# Schematic_SHERPA.net
KiCad netlist of a schematic drawn in Altium Designer
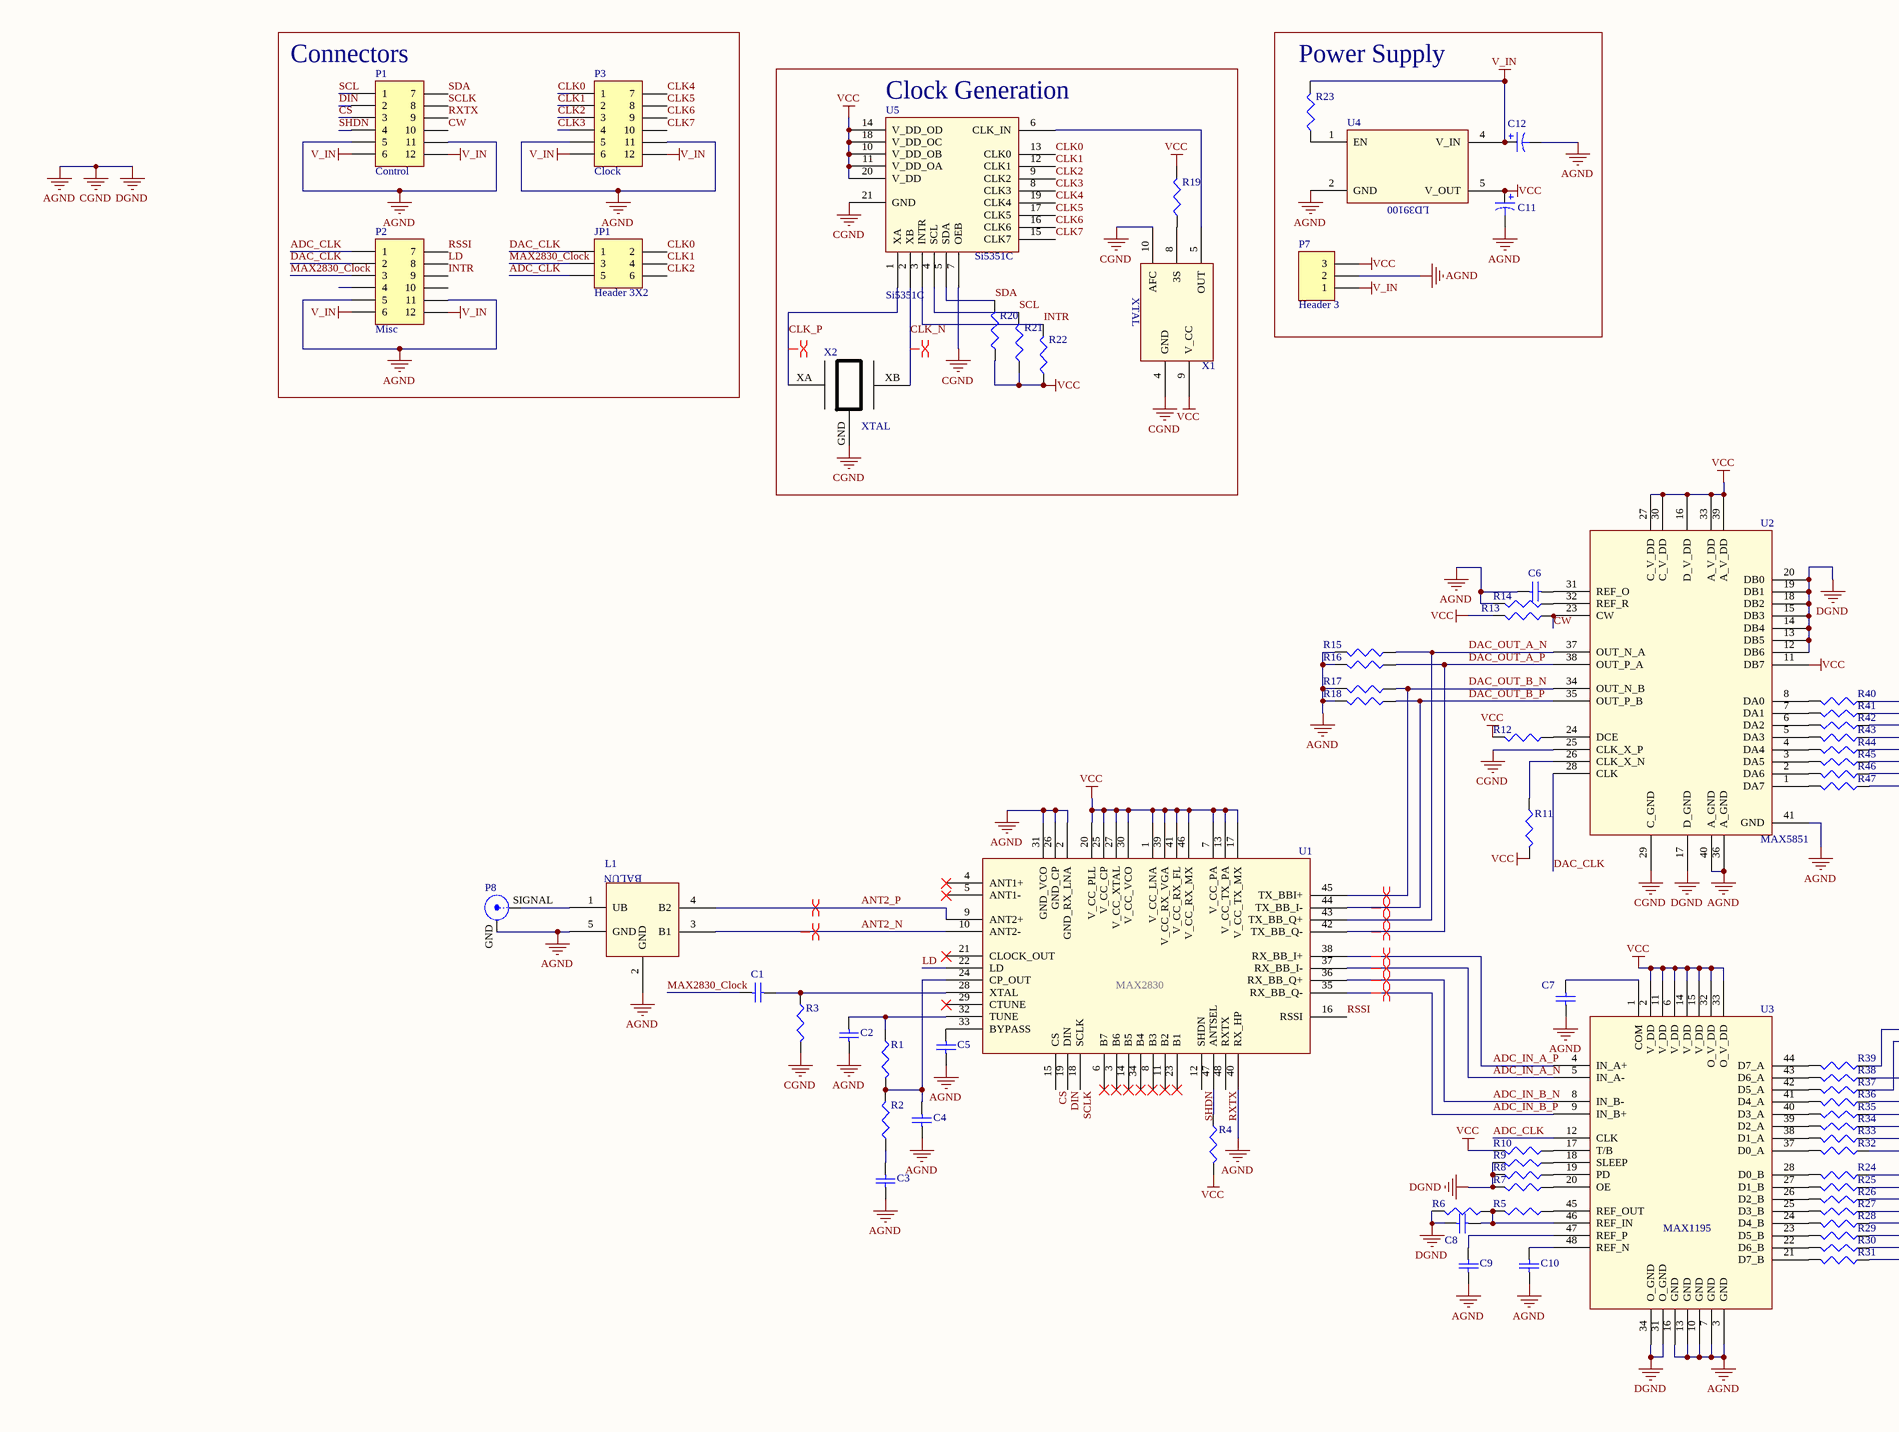
[diagram p0: Schematic_SHERPA.SchDoc, left]
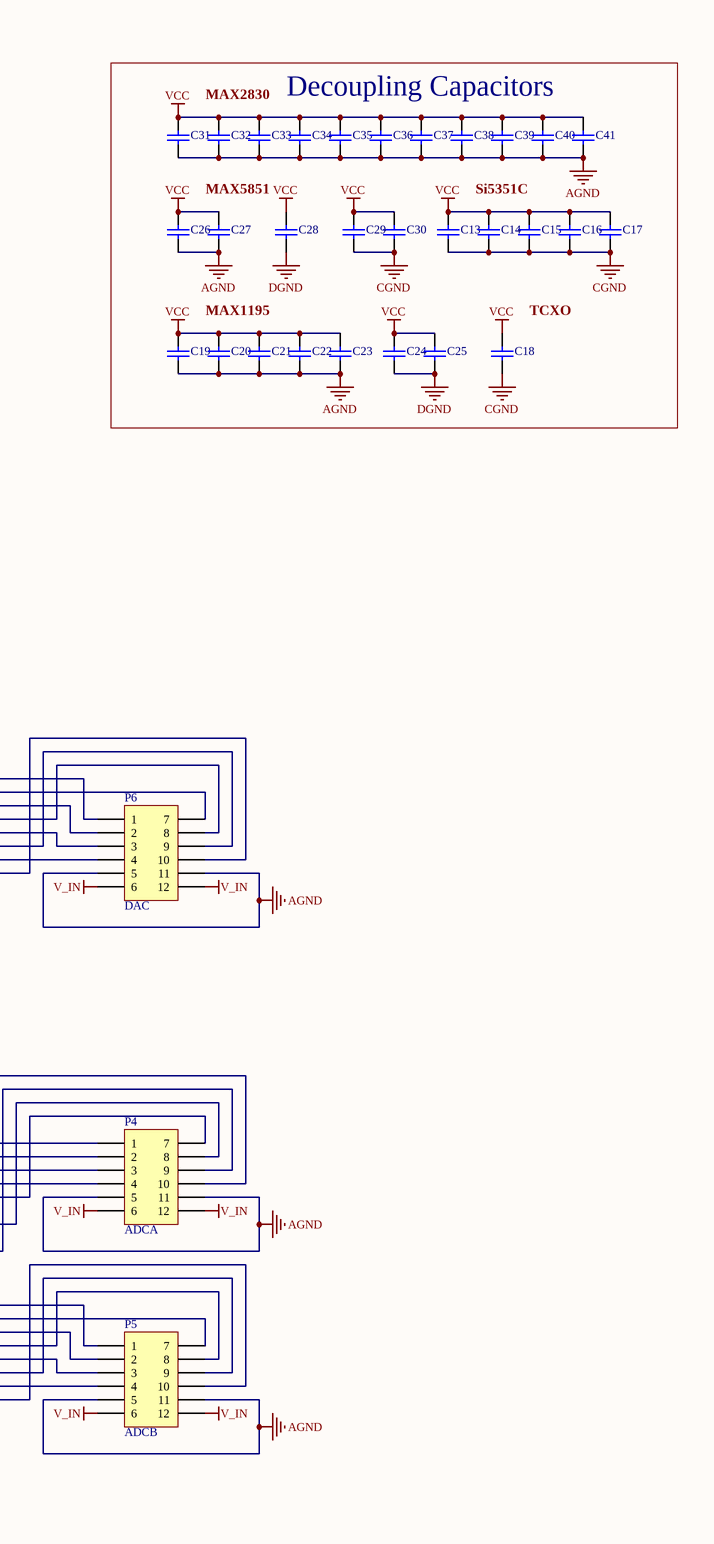
[diagram p1: Schematic_SHERPA.SchDoc, right]

(export (version "E")
  (design (tool "Eeschema 10.0.6"))
  (components
    (comp (ref "C1")
      (value "Cap Semi")
      (footprint "0402")
      (description "Capacitor (Semiconductor SIM Model)")
      (fields (field (name "PUBLISHER") "Altium Limited"))
      (libsource (lib "Miscellaneous Devices") (part "Cap Semi"))
    )
    (comp (ref "C2")
      (value "Cap Semi")
      (footprint "0402")
      (description "Capacitor (Semiconductor SIM Model)")
      (fields (field (name "PUBLISHER") "Altium Limited"))
      (libsource (lib "Miscellaneous Devices") (part "Cap Semi"))
    )
    (comp (ref "C3")
      (value "Cap Semi")
      (footprint "0402")
      (description "Capacitor (Semiconductor SIM Model)")
      (fields (field (name "PUBLISHER") "Altium Limited"))
      (libsource (lib "Miscellaneous Devices") (part "Cap Semi"))
    )
    (comp (ref "C4")
      (value "Cap Semi")
      (footprint "0402")
      (description "Capacitor (Semiconductor SIM Model)")
      (fields (field (name "PUBLISHER") "Altium Limited"))
      (libsource (lib "Miscellaneous Devices") (part "Cap Semi"))
    )
    (comp (ref "C5")
      (value "Cap Semi")
      (footprint "0402")
      (description "Capacitor (Semiconductor SIM Model)")
      (fields (field (name "PUBLISHER") "Altium Limited"))
      (libsource (lib "Miscellaneous Devices") (part "Cap Semi"))
    )
    (comp (ref "C6")
      (value "Cap Semi")
      (footprint "0402")
      (description "Capacitor (Semiconductor SIM Model)")
      (fields (field (name "PUBLISHER") "Altium Limited"))
      (libsource (lib "Miscellaneous Devices") (part "Cap Semi"))
    )
    (comp (ref "C7")
      (value "Cap Semi")
      (footprint "0402")
      (description "Capacitor (Semiconductor SIM Model)")
      (fields (field (name "PUBLISHER") "Altium Limited"))
      (libsource (lib "Miscellaneous Devices") (part "Cap Semi"))
    )
    (comp (ref "C8")
      (value "Cap Semi")
      (footprint "0402")
      (description "Capacitor (Semiconductor SIM Model)")
      (fields (field (name "PUBLISHER") "Altium Limited"))
      (libsource (lib "Miscellaneous Devices") (part "Cap Semi"))
    )
    (comp (ref "C9")
      (value "Cap Semi")
      (footprint "0402")
      (description "Capacitor (Semiconductor SIM Model)")
      (fields (field (name "PUBLISHER") "Altium Limited"))
      (libsource (lib "Miscellaneous Devices") (part "Cap Semi"))
    )
    (comp (ref "C10")
      (value "Cap Semi")
      (footprint "0402")
      (description "Capacitor (Semiconductor SIM Model)")
      (fields (field (name "PUBLISHER") "Altium Limited"))
      (libsource (lib "Miscellaneous Devices") (part "Cap Semi"))
    )
    (comp (ref "C11")
      (value "Cap Pol3")
      (footprint "C0805")
      (description "Polarized Capacitor (Surface Mount)")
      (fields (field (name "PUBLISHER") "Altium Limited"))
      (libsource (lib "Miscellaneous Devices") (part "Cap Pol3"))
    )
    (comp (ref "C12")
      (value "Cap Pol3")
      (footprint "C0805")
      (description "Polarized Capacitor (Surface Mount)")
      (fields (field (name "PUBLISHER") "Altium Limited"))
      (libsource (lib "Miscellaneous Devices") (part "Cap Pol3"))
    )
    (comp (ref "C13")
      (value "Cap Semi")
      (footprint "0402")
      (description "Capacitor (Semiconductor SIM Model)")
      (fields (field (name "PUBLISHER") "Altium Limited"))
      (libsource (lib "Miscellaneous Devices") (part "Cap Semi"))
    )
    (comp (ref "C14")
      (value "Cap Semi")
      (footprint "0402")
      (description "Capacitor (Semiconductor SIM Model)")
      (fields (field (name "PUBLISHER") "Altium Limited"))
      (libsource (lib "Miscellaneous Devices") (part "Cap Semi"))
    )
    (comp (ref "C15")
      (value "Cap Semi")
      (footprint "0402")
      (description "Capacitor (Semiconductor SIM Model)")
      (fields (field (name "PUBLISHER") "Altium Limited"))
      (libsource (lib "Miscellaneous Devices") (part "Cap Semi"))
    )
    (comp (ref "C16")
      (value "Cap Semi")
      (footprint "0402")
      (description "Capacitor (Semiconductor SIM Model)")
      (fields (field (name "PUBLISHER") "Altium Limited"))
      (libsource (lib "Miscellaneous Devices") (part "Cap Semi"))
    )
    (comp (ref "C17")
      (value "Cap Semi")
      (footprint "0402")
      (description "Capacitor (Semiconductor SIM Model)")
      (fields (field (name "PUBLISHER") "Altium Limited"))
      (libsource (lib "Miscellaneous Devices") (part "Cap Semi"))
    )
    (comp (ref "C18")
      (value "Cap Semi")
      (footprint "0402")
      (description "Capacitor (Semiconductor SIM Model)")
      (fields (field (name "PUBLISHER") "Altium Limited"))
      (libsource (lib "Miscellaneous Devices") (part "Cap Semi"))
    )
    (comp (ref "C19")
      (value "Cap Semi")
      (footprint "0402")
      (description "Capacitor (Semiconductor SIM Model)")
      (fields (field (name "PUBLISHER") "Altium Limited"))
      (libsource (lib "Miscellaneous Devices") (part "Cap Semi"))
    )
    (comp (ref "C20")
      (value "Cap Semi")
      (footprint "0402")
      (description "Capacitor (Semiconductor SIM Model)")
      (fields (field (name "PUBLISHER") "Altium Limited"))
      (libsource (lib "Miscellaneous Devices") (part "Cap Semi"))
    )
    (comp (ref "C21")
      (value "Cap Semi")
      (footprint "0402")
      (description "Capacitor (Semiconductor SIM Model)")
      (fields (field (name "PUBLISHER") "Altium Limited"))
      (libsource (lib "Miscellaneous Devices") (part "Cap Semi"))
    )
    (comp (ref "C22")
      (value "Cap Semi")
      (footprint "0402")
      (description "Capacitor (Semiconductor SIM Model)")
      (fields (field (name "PUBLISHER") "Altium Limited"))
      (libsource (lib "Miscellaneous Devices") (part "Cap Semi"))
    )
    (comp (ref "C23")
      (value "Cap Semi")
      (footprint "0402")
      (description "Capacitor (Semiconductor SIM Model)")
      (fields (field (name "PUBLISHER") "Altium Limited"))
      (libsource (lib "Miscellaneous Devices") (part "Cap Semi"))
    )
    (comp (ref "C24")
      (value "Cap Semi")
      (footprint "0402")
      (description "Capacitor (Semiconductor SIM Model)")
      (fields (field (name "PUBLISHER") "Altium Limited"))
      (libsource (lib "Miscellaneous Devices") (part "Cap Semi"))
    )
    (comp (ref "C25")
      (value "Cap Semi")
      (footprint "0402")
      (description "Capacitor (Semiconductor SIM Model)")
      (fields (field (name "PUBLISHER") "Altium Limited"))
      (libsource (lib "Miscellaneous Devices") (part "Cap Semi"))
    )
    (comp (ref "C26")
      (value "Cap Semi")
      (footprint "0402")
      (description "Capacitor (Semiconductor SIM Model)")
      (fields (field (name "PUBLISHER") "Altium Limited"))
      (libsource (lib "Miscellaneous Devices") (part "Cap Semi"))
    )
    (comp (ref "C27")
      (value "Cap Semi")
      (footprint "0402")
      (description "Capacitor (Semiconductor SIM Model)")
      (fields (field (name "PUBLISHER") "Altium Limited"))
      (libsource (lib "Miscellaneous Devices") (part "Cap Semi"))
    )
    (comp (ref "C28")
      (value "Cap Semi")
      (footprint "0402")
      (description "Capacitor (Semiconductor SIM Model)")
      (fields (field (name "PUBLISHER") "Altium Limited"))
      (libsource (lib "Miscellaneous Devices") (part "Cap Semi"))
    )
    (comp (ref "C29")
      (value "Cap Semi")
      (footprint "0402")
      (description "Capacitor (Semiconductor SIM Model)")
      (fields (field (name "PUBLISHER") "Altium Limited"))
      (libsource (lib "Miscellaneous Devices") (part "Cap Semi"))
    )
    (comp (ref "C30")
      (value "Cap Semi")
      (footprint "0402")
      (description "Capacitor (Semiconductor SIM Model)")
      (fields (field (name "PUBLISHER") "Altium Limited"))
      (libsource (lib "Miscellaneous Devices") (part "Cap Semi"))
    )
    (comp (ref "C31")
      (value "Cap Semi")
      (footprint "0402")
      (description "Capacitor (Semiconductor SIM Model)")
      (fields (field (name "PUBLISHER") "Altium Limited"))
      (libsource (lib "Miscellaneous Devices") (part "Cap Semi"))
    )
    (comp (ref "C32")
      (value "Cap Semi")
      (footprint "0402")
      (description "Capacitor (Semiconductor SIM Model)")
      (fields (field (name "PUBLISHER") "Altium Limited"))
      (libsource (lib "Miscellaneous Devices") (part "Cap Semi"))
    )
    (comp (ref "C33")
      (value "Cap Semi")
      (footprint "0402")
      (description "Capacitor (Semiconductor SIM Model)")
      (fields (field (name "PUBLISHER") "Altium Limited"))
      (libsource (lib "Miscellaneous Devices") (part "Cap Semi"))
    )
    (comp (ref "C34")
      (value "Cap Semi")
      (footprint "0402")
      (description "Capacitor (Semiconductor SIM Model)")
      (fields (field (name "PUBLISHER") "Altium Limited"))
      (libsource (lib "Miscellaneous Devices") (part "Cap Semi"))
    )
    (comp (ref "C35")
      (value "Cap Semi")
      (footprint "0402")
      (description "Capacitor (Semiconductor SIM Model)")
      (fields (field (name "PUBLISHER") "Altium Limited"))
      (libsource (lib "Miscellaneous Devices") (part "Cap Semi"))
    )
    (comp (ref "C36")
      (value "Cap Semi")
      (footprint "0402")
      (description "Capacitor (Semiconductor SIM Model)")
      (fields (field (name "PUBLISHER") "Altium Limited"))
      (libsource (lib "Miscellaneous Devices") (part "Cap Semi"))
    )
    (comp (ref "C37")
      (value "Cap Semi")
      (footprint "0402")
      (description "Capacitor (Semiconductor SIM Model)")
      (fields (field (name "PUBLISHER") "Altium Limited"))
      (libsource (lib "Miscellaneous Devices") (part "Cap Semi"))
    )
    (comp (ref "C38")
      (value "Cap Semi")
      (footprint "0402")
      (description "Capacitor (Semiconductor SIM Model)")
      (fields (field (name "PUBLISHER") "Altium Limited"))
      (libsource (lib "Miscellaneous Devices") (part "Cap Semi"))
    )
    (comp (ref "C39")
      (value "Cap Semi")
      (footprint "0402")
      (description "Capacitor (Semiconductor SIM Model)")
      (fields (field (name "PUBLISHER") "Altium Limited"))
      (libsource (lib "Miscellaneous Devices") (part "Cap Semi"))
    )
    (comp (ref "C40")
      (value "Cap Semi")
      (footprint "0402")
      (description "Capacitor (Semiconductor SIM Model)")
      (fields (field (name "PUBLISHER") "Altium Limited"))
      (libsource (lib "Miscellaneous Devices") (part "Cap Semi"))
    )
    (comp (ref "C41")
      (value "Cap Semi")
      (footprint "0402")
      (description "Capacitor (Semiconductor SIM Model)")
      (fields (field (name "PUBLISHER") "Altium Limited"))
      (libsource (lib "Miscellaneous Devices") (part "Cap Semi"))
    )
    (comp (ref "JP1")
      (value "Header 3X2")
      (footprint "HDR2X3")
      (description "Header, 3-Pin, Dual row")
      (fields (field (name "PUBLISHER") "Altium Limited"))
      (libsource (lib "Miscellaneous Connectors") (part "Header 3X2"))
    )
    (comp (ref "L1")
      (value "BALUN_2")
      (footprint "BALUN2")
      (libsource (lib "Schlib_SHERPA") (part "BALUN_2"))
    )
    (comp (ref "P1")
      (value "Control")
      (footprint "HDR2X6_CEN")
      (description "Header, 6-Pin, Dual row")
      (fields (field (name "PUBLISHER") "Altium Limited"))
      (libsource (lib "Miscellaneous Connectors") (part "Header 6X2A"))
    )
    (comp (ref "P2")
      (value "Misc")
      (footprint "HDR2X6_CEN")
      (description "Header, 6-Pin, Dual row")
      (fields (field (name "PUBLISHER") "Altium Limited"))
      (libsource (lib "Miscellaneous Connectors") (part "Header 6X2A"))
    )
    (comp (ref "P3")
      (value "Clock")
      (footprint "HDR2X6_CEN")
      (description "Header, 6-Pin, Dual row")
      (fields (field (name "PUBLISHER") "Altium Limited"))
      (libsource (lib "Miscellaneous Connectors") (part "Header 6X2A"))
    )
    (comp (ref "P4")
      (value "ADCA")
      (footprint "HDR2X6_CEN")
      (description "Header, 6-Pin, Dual row")
      (fields (field (name "PUBLISHER") "Altium Limited"))
      (libsource (lib "Miscellaneous Connectors") (part "Header 6X2A"))
    )
    (comp (ref "P5")
      (value "ADCB")
      (footprint "HDR2X6_CEN")
      (description "Header, 6-Pin, Dual row")
      (fields (field (name "PUBLISHER") "Altium Limited"))
      (libsource (lib "Miscellaneous Connectors") (part "Header 6X2A"))
    )
    (comp (ref "P6")
      (value "DAC")
      (footprint "HDR2X6_CEN")
      (description "Header, 6-Pin, Dual row")
      (fields (field (name "PUBLISHER") "Altium Limited"))
      (libsource (lib "Miscellaneous Connectors") (part "Header 6X2A"))
    )
    (comp (ref "P7")
      (value "Header 3")
      (footprint "HDR1X3")
      (description "Header, 3-Pin")
      (fields (field (name "PUBLISHER") "Altium Limited"))
      (libsource (lib "Miscellaneous Connectors") (part "Header 3"))
    )
    (comp (ref "P8")
      (value "SMA")
      (footprint "SMA Connector")
      (description "BNC Elbow Connector")
      (fields (field (name "PUBLISHER") "Altium Limited"))
      (libsource (lib "Miscellaneous Connectors") (part "BNC"))
    )
    (comp (ref "R1")
      (value "Res3")
      (footprint "0402")
      (description "Resistor")
      (fields (field (name "PUBLISHER") "Altium Limited"))
      (libsource (lib "Miscellaneous Devices") (part "Res3"))
    )
    (comp (ref "R2")
      (value "Res3")
      (footprint "0402")
      (description "Resistor")
      (fields (field (name "PUBLISHER") "Altium Limited"))
      (libsource (lib "Miscellaneous Devices") (part "Res3"))
    )
    (comp (ref "R3")
      (value "Res3")
      (footprint "0402")
      (description "Resistor")
      (fields (field (name "PUBLISHER") "Altium Limited"))
      (libsource (lib "Miscellaneous Devices") (part "Res3"))
    )
    (comp (ref "R4")
      (value "Res3")
      (footprint "0402")
      (description "Resistor")
      (fields (field (name "PUBLISHER") "Altium Limited"))
      (libsource (lib "Miscellaneous Devices") (part "Res3"))
    )
    (comp (ref "R5")
      (value "Res3")
      (footprint "0402")
      (description "Resistor")
      (fields (field (name "PUBLISHER") "Altium Limited"))
      (libsource (lib "Miscellaneous Devices") (part "Res3"))
    )
    (comp (ref "R6")
      (value "Res3")
      (footprint "0402")
      (description "Resistor")
      (fields (field (name "PUBLISHER") "Altium Limited"))
      (libsource (lib "Miscellaneous Devices") (part "Res3"))
    )
    (comp (ref "R7")
      (value "Res3")
      (footprint "0402")
      (description "Resistor")
      (fields (field (name "PUBLISHER") "Altium Limited"))
      (libsource (lib "Miscellaneous Devices") (part "Res3"))
    )
    (comp (ref "R8")
      (value "Res3")
      (footprint "0402")
      (description "Resistor")
      (fields (field (name "PUBLISHER") "Altium Limited"))
      (libsource (lib "Miscellaneous Devices") (part "Res3"))
    )
    (comp (ref "R9")
      (value "Res3")
      (footprint "0402")
      (description "Resistor")
      (fields (field (name "PUBLISHER") "Altium Limited"))
      (libsource (lib "Miscellaneous Devices") (part "Res3"))
    )
    (comp (ref "R10")
      (value "Res3")
      (footprint "0402")
      (description "Resistor")
      (fields (field (name "PUBLISHER") "Altium Limited"))
      (libsource (lib "Miscellaneous Devices") (part "Res3"))
    )
    (comp (ref "R11")
      (value "Res3")
      (footprint "0402")
      (description "Resistor")
      (fields (field (name "PUBLISHER") "Altium Limited"))
      (libsource (lib "Miscellaneous Devices") (part "Res3"))
    )
    (comp (ref "R12")
      (value "Res3")
      (footprint "0402")
      (description "Resistor")
      (fields (field (name "PUBLISHER") "Altium Limited"))
      (libsource (lib "Miscellaneous Devices") (part "Res3"))
    )
    (comp (ref "R13")
      (value "Res3")
      (footprint "0402")
      (description "Resistor")
      (fields (field (name "PUBLISHER") "Altium Limited"))
      (libsource (lib "Miscellaneous Devices") (part "Res3"))
    )
    (comp (ref "R14")
      (value "Res3")
      (footprint "0402")
      (description "Resistor")
      (fields (field (name "PUBLISHER") "Altium Limited"))
      (libsource (lib "Miscellaneous Devices") (part "Res3"))
    )
    (comp (ref "R15")
      (value "Res3")
      (footprint "0402")
      (description "Resistor")
      (fields (field (name "PUBLISHER") "Altium Limited"))
      (libsource (lib "Miscellaneous Devices") (part "Res3"))
    )
    (comp (ref "R16")
      (value "Res3")
      (footprint "0402")
      (description "Resistor")
      (fields (field (name "PUBLISHER") "Altium Limited"))
      (libsource (lib "Miscellaneous Devices") (part "Res3"))
    )
    (comp (ref "R17")
      (value "Res3")
      (footprint "0402")
      (description "Resistor")
      (fields (field (name "PUBLISHER") "Altium Limited"))
      (libsource (lib "Miscellaneous Devices") (part "Res3"))
    )
    (comp (ref "R18")
      (value "Res3")
      (footprint "0402")
      (description "Resistor")
      (fields (field (name "PUBLISHER") "Altium Limited"))
      (libsource (lib "Miscellaneous Devices") (part "Res3"))
    )
    (comp (ref "R19")
      (value "Res3")
      (footprint "0402")
      (description "Resistor")
      (fields (field (name "PUBLISHER") "Altium Limited"))
      (libsource (lib "Miscellaneous Devices") (part "Res3"))
    )
    (comp (ref "R20")
      (value "Res3")
      (footprint "0402")
      (description "Resistor")
      (fields (field (name "PUBLISHER") "Altium Limited"))
      (libsource (lib "Miscellaneous Devices") (part "Res3"))
    )
    (comp (ref "R21")
      (value "Res3")
      (footprint "0402")
      (description "Resistor")
      (fields (field (name "PUBLISHER") "Altium Limited"))
      (libsource (lib "Miscellaneous Devices") (part "Res3"))
    )
    (comp (ref "R22")
      (value "Res3")
      (footprint "0402")
      (description "Resistor")
      (fields (field (name "PUBLISHER") "Altium Limited"))
      (libsource (lib "Miscellaneous Devices") (part "Res3"))
    )
    (comp (ref "R23")
      (value "Res3")
      (footprint "0402")
      (description "Resistor")
      (fields (field (name "PUBLISHER") "Altium Limited"))
      (libsource (lib "Miscellaneous Devices") (part "Res3"))
    )
    (comp (ref "R24")
      (value "Res3")
      (footprint "0402")
      (description "Resistor")
      (fields (field (name "PUBLISHER") "Altium Limited"))
      (libsource (lib "Miscellaneous Devices") (part "Res3"))
    )
    (comp (ref "R25")
      (value "Res3")
      (footprint "0402")
      (description "Resistor")
      (fields (field (name "PUBLISHER") "Altium Limited"))
      (libsource (lib "Miscellaneous Devices") (part "Res3"))
    )
    (comp (ref "R26")
      (value "Res3")
      (footprint "0402")
      (description "Resistor")
      (fields (field (name "PUBLISHER") "Altium Limited"))
      (libsource (lib "Miscellaneous Devices") (part "Res3"))
    )
    (comp (ref "R27")
      (value "Res3")
      (footprint "0402")
      (description "Resistor")
      (fields (field (name "PUBLISHER") "Altium Limited"))
      (libsource (lib "Miscellaneous Devices") (part "Res3"))
    )
    (comp (ref "R28")
      (value "Res3")
      (footprint "0402")
      (description "Resistor")
      (fields (field (name "PUBLISHER") "Altium Limited"))
      (libsource (lib "Miscellaneous Devices") (part "Res3"))
    )
    (comp (ref "R29")
      (value "Res3")
      (footprint "0402")
      (description "Resistor")
      (fields (field (name "PUBLISHER") "Altium Limited"))
      (libsource (lib "Miscellaneous Devices") (part "Res3"))
    )
    (comp (ref "R30")
      (value "Res3")
      (footprint "0402")
      (description "Resistor")
      (fields (field (name "PUBLISHER") "Altium Limited"))
      (libsource (lib "Miscellaneous Devices") (part "Res3"))
    )
    (comp (ref "R31")
      (value "Res3")
      (footprint "0402")
      (description "Resistor")
      (fields (field (name "PUBLISHER") "Altium Limited"))
      (libsource (lib "Miscellaneous Devices") (part "Res3"))
    )
    (comp (ref "R32")
      (value "Res3")
      (footprint "0402")
      (description "Resistor")
      (fields (field (name "PUBLISHER") "Altium Limited"))
      (libsource (lib "Miscellaneous Devices") (part "Res3"))
    )
    (comp (ref "R33")
      (value "Res3")
      (footprint "0402")
      (description "Resistor")
      (fields (field (name "PUBLISHER") "Altium Limited"))
      (libsource (lib "Miscellaneous Devices") (part "Res3"))
    )
    (comp (ref "R34")
      (value "Res3")
      (footprint "0402")
      (description "Resistor")
      (fields (field (name "PUBLISHER") "Altium Limited"))
      (libsource (lib "Miscellaneous Devices") (part "Res3"))
    )
    (comp (ref "R35")
      (value "Res3")
      (footprint "0402")
      (description "Resistor")
      (fields (field (name "PUBLISHER") "Altium Limited"))
      (libsource (lib "Miscellaneous Devices") (part "Res3"))
    )
    (comp (ref "R36")
      (value "Res3")
      (footprint "0402")
      (description "Resistor")
      (fields (field (name "PUBLISHER") "Altium Limited"))
      (libsource (lib "Miscellaneous Devices") (part "Res3"))
    )
    (comp (ref "R37")
      (value "Res3")
      (footprint "0402")
      (description "Resistor")
      (fields (field (name "PUBLISHER") "Altium Limited"))
      (libsource (lib "Miscellaneous Devices") (part "Res3"))
    )
    (comp (ref "R38")
      (value "Res3")
      (footprint "0402")
      (description "Resistor")
      (fields (field (name "PUBLISHER") "Altium Limited"))
      (libsource (lib "Miscellaneous Devices") (part "Res3"))
    )
    (comp (ref "R39")
      (value "Res3")
      (footprint "0402")
      (description "Resistor")
      (fields (field (name "PUBLISHER") "Altium Limited"))
      (libsource (lib "Miscellaneous Devices") (part "Res3"))
    )
    (comp (ref "R40")
      (value "Res3")
      (footprint "0402")
      (description "Resistor")
      (fields (field (name "PUBLISHER") "Altium Limited"))
      (libsource (lib "Miscellaneous Devices") (part "Res3"))
    )
    (comp (ref "R41")
      (value "Res3")
      (footprint "0402")
      (description "Resistor")
      (fields (field (name "PUBLISHER") "Altium Limited"))
      (libsource (lib "Miscellaneous Devices") (part "Res3"))
    )
    (comp (ref "R42")
      (value "Res3")
      (footprint "0402")
      (description "Resistor")
      (fields (field (name "PUBLISHER") "Altium Limited"))
      (libsource (lib "Miscellaneous Devices") (part "Res3"))
    )
    (comp (ref "R43")
      (value "Res3")
      (footprint "0402")
      (description "Resistor")
      (fields (field (name "PUBLISHER") "Altium Limited"))
      (libsource (lib "Miscellaneous Devices") (part "Res3"))
    )
    (comp (ref "R44")
      (value "Res3")
      (footprint "0402")
      (description "Resistor")
      (fields (field (name "PUBLISHER") "Altium Limited"))
      (libsource (lib "Miscellaneous Devices") (part "Res3"))
    )
    (comp (ref "R45")
      (value "Res3")
      (footprint "0402")
      (description "Resistor")
      (fields (field (name "PUBLISHER") "Altium Limited"))
      (libsource (lib "Miscellaneous Devices") (part "Res3"))
    )
    (comp (ref "R46")
      (value "Res3")
      (footprint "0402")
      (description "Resistor")
      (fields (field (name "PUBLISHER") "Altium Limited"))
      (libsource (lib "Miscellaneous Devices") (part "Res3"))
    )
    (comp (ref "R47")
      (value "Res3")
      (footprint "0402")
      (description "Resistor")
      (fields (field (name "PUBLISHER") "Altium Limited"))
      (libsource (lib "Miscellaneous Devices") (part "Res3"))
    )
    (comp (ref "U1")
      (value "MAX2830")
      (footprint "MAX2830")
      (libsource (lib "Schlib_SHERPA") (part "MAX2830"))
    )
    (comp (ref "U2")
      (value "MAX5851")
      (footprint "MAX5851")
      (libsource (lib "Schlib_SHERPA") (part "MAX5851"))
    )
    (comp (ref "U3")
      (value "MAX1195")
      (footprint "MAX1195")
      (libsource (lib "Schlib_SHERPA") (part "MAX1195"))
    )
    (comp (ref "U4") (value "XD6220") (footprint "XC 6220") (libsource (lib "Schlib_SHERPA") (part "XD6220")))
    (comp (ref "U5")
      (value "Si5351C")
      (footprint "Si5351C")
      (libsource (lib "Schlib_SHERPA") (part "Si5351C"))
    )
    (comp (ref "X1")
      (value "7N-25.000MBP-T")
      (footprint "7N-25.000MBP-T")
      (libsource (lib "Schlib_SHERPA") (part "7N-25.000MBP-T"))
    )
    (comp (ref "X2") (value "XTAL") (footprint "XTAL") (libsource (lib "Schlib_SHERPA") (part "XTAL")))
  )
  (nets
    (net (code "1") (name "/ADC_CLK") (class "Default")
      (node (ref "JP1") (pin "5") (pinfunction "5_5") (pintype "passive"))
      (node (ref "P2") (pin "1") (pinfunction "1_1") (pintype "passive"))
      (node (ref "U3") (pin "12") (pinfunction "CLK_12") (pintype "passive"))
    )
    (net (code "2") (name "/ADC_IN_A_N") (class "Default")
      (node (ref "U1") (pin "37") (pinfunction "RX_BB_I-_37") (pintype "passive"))
      (node (ref "U3") (pin "5") (pinfunction "IN_A-_5") (pintype "passive"))
    )
    (net (code "3") (name "/ADC_IN_A_P") (class "Default")
      (node (ref "U1") (pin "38") (pinfunction "RX_BB_I+_38") (pintype "passive"))
      (node (ref "U3") (pin "4") (pinfunction "IN_A+_4") (pintype "passive"))
    )
    (net (code "4") (name "/ADC_IN_B_N") (class "Default")
      (node (ref "U1") (pin "36") (pinfunction "RX_BB_Q+_36") (pintype "passive"))
      (node (ref "U3") (pin "8") (pinfunction "IN_B-_8") (pintype "passive"))
    )
    (net (code "5") (name "/ADC_IN_B_P") (class "Default")
      (node (ref "U1") (pin "35") (pinfunction "RX_BB_Q-_35") (pintype "passive"))
      (node (ref "U3") (pin "9") (pinfunction "IN_B+_9") (pintype "passive"))
    )
    (net (code "6") (name "/ANT2_N") (class "Default")
      (node (ref "L1") (pin "3") (pinfunction "B1_3") (pintype "passive"))
      (node (ref "U1") (pin "10") (pinfunction "ANT2-_10") (pintype "passive"))
    )
    (net (code "7") (name "/ANT2_P") (class "Default")
      (node (ref "L1") (pin "4") (pinfunction "B2_4") (pintype "passive"))
      (node (ref "U1") (pin "9") (pinfunction "ANT2+_9") (pintype "passive"))
    )
    (net (code "8") (name "/CLK0") (class "Default")
      (node (ref "JP1") (pin "2") (pinfunction "2_2") (pintype "passive"))
      (node (ref "P3") (pin "1") (pinfunction "1_1") (pintype "passive"))
      (node (ref "U5") (pin "13") (pinfunction "CLK0_13") (pintype "passive"))
    )
    (net (code "9") (name "/CLK1") (class "Default")
      (node (ref "JP1") (pin "4") (pinfunction "4_4") (pintype "passive"))
      (node (ref "P3") (pin "2") (pinfunction "2_2") (pintype "passive"))
      (node (ref "U5") (pin "12") (pinfunction "CLK1_12") (pintype "passive"))
    )
    (net (code "10") (name "/CLK2") (class "Default")
      (node (ref "JP1") (pin "6") (pinfunction "6_6") (pintype "passive"))
      (node (ref "P3") (pin "3") (pinfunction "3_3") (pintype "passive"))
      (node (ref "U5") (pin "9") (pinfunction "CLK2_9") (pintype "passive"))
    )
    (net (code "11") (name "/CLK3") (class "Default")
      (node (ref "P3") (pin "4") (pinfunction "4_4") (pintype "passive"))
      (node (ref "U5") (pin "8") (pinfunction "CLK3_8") (pintype "passive"))
    )
    (net (code "12") (name "/CLK4") (class "Default")
      (node (ref "P3") (pin "7") (pinfunction "7_7") (pintype "passive"))
      (node (ref "U5") (pin "19") (pinfunction "CLK4_19") (pintype "passive"))
    )
    (net (code "13") (name "/CLK5") (class "Default")
      (node (ref "P3") (pin "8") (pinfunction "8_8") (pintype "passive"))
      (node (ref "U5") (pin "17") (pinfunction "CLK5_17") (pintype "passive"))
    )
    (net (code "14") (name "/CLK6") (class "Default")
      (node (ref "P3") (pin "9") (pinfunction "9_9") (pintype "passive"))
      (node (ref "U5") (pin "16") (pinfunction "CLK6_16") (pintype "passive"))
    )
    (net (code "15") (name "/CLK7") (class "Default")
      (node (ref "P3") (pin "10") (pinfunction "10_10") (pintype "passive"))
      (node (ref "U5") (pin "15") (pinfunction "CLK7_15") (pintype "passive"))
    )
    (net (code "16") (name "/CLK_N") (class "Default")
      (node (ref "U5") (pin "2") (pinfunction "XB_2") (pintype "passive"))
      (node (ref "X2") (pin "XB") (pinfunction "XB_XB") (pintype "passive"))
    )
    (net (code "17") (name "/CLK_P") (class "Default")
      (node (ref "U5") (pin "1") (pinfunction "XA_1") (pintype "passive"))
      (node (ref "X2") (pin "XA") (pinfunction "XA_XA") (pintype "passive"))
    )
    (net (code "18") (name "/CS") (class "Default")
      (node (ref "P1") (pin "3") (pinfunction "3_3") (pintype "passive"))
      (node (ref "U1") (pin "15") (pinfunction "CS_15") (pintype "passive"))
    )
    (net (code "19") (name "/CW") (class "Default")
      (node (ref "P1") (pin "10") (pinfunction "10_10") (pintype "passive"))
      (node (ref "R13") (pin "1") (pinfunction "1_1") (pintype "passive"))
      (node (ref "U2") (pin "23") (pinfunction "CW_23") (pintype "passive"))
    )
    (net (code "20") (name "/DAC_CLK") (class "Default")
      (node (ref "JP1") (pin "1") (pinfunction "1_1") (pintype "passive"))
      (node (ref "P2") (pin "2") (pinfunction "2_2") (pintype "passive"))
      (node (ref "U2") (pin "28") (pinfunction "CLK_28") (pintype "passive"))
    )
    (net (code "21") (name "/DAC_OUT_A_N") (class "Default")
      (node (ref "R15") (pin "1") (pinfunction "1_1") (pintype "passive"))
      (node (ref "U1") (pin "43") (pinfunction "TX_BB_Q+_43") (pintype "passive"))
      (node (ref "U2") (pin "37") (pinfunction "OUT_N_A_37") (pintype "passive"))
    )
    (net (code "22") (name "/DAC_OUT_A_P") (class "Default")
      (node (ref "R16") (pin "1") (pinfunction "1_1") (pintype "passive"))
      (node (ref "U1") (pin "42") (pinfunction "TX_BB_Q-_42") (pintype "passive"))
      (node (ref "U2") (pin "38") (pinfunction "OUT_P_A_38") (pintype "passive"))
    )
    (net (code "23") (name "/DAC_OUT_B_N") (class "Default")
      (node (ref "R17") (pin "1") (pinfunction "1_1") (pintype "passive"))
      (node (ref "U1") (pin "45") (pinfunction "TX_BBI+_45") (pintype "passive"))
      (node (ref "U2") (pin "34") (pinfunction "OUT_N_B_34") (pintype "passive"))
    )
    (net (code "24") (name "/DAC_OUT_B_P") (class "Default")
      (node (ref "R18") (pin "1") (pinfunction "1_1") (pintype "passive"))
      (node (ref "U1") (pin "44") (pinfunction "TX_BB_I-_44") (pintype "passive"))
      (node (ref "U2") (pin "35") (pinfunction "OUT_P_B_35") (pintype "passive"))
    )
    (net (code "25") (name "/DIN") (class "Default")
      (node (ref "P1") (pin "2") (pinfunction "2_2") (pintype "passive"))
      (node (ref "U1") (pin "19") (pinfunction "DIN_19") (pintype "passive"))
    )
    (net (code "26") (name "/INTR") (class "Default")
      (node (ref "P2") (pin "9") (pinfunction "9_9") (pintype "passive"))
      (node (ref "R22") (pin "2") (pinfunction "2_2") (pintype "passive"))
      (node (ref "U5") (pin "3") (pinfunction "INTR_3") (pintype "passive"))
    )
    (net (code "27") (name "/LD") (class "Default")
      (node (ref "P2") (pin "8") (pinfunction "8_8") (pintype "passive"))
      (node (ref "U1") (pin "22") (pinfunction "LD_22") (pintype "passive"))
    )
    (net (code "28") (name "/MAX2830_Clock") (class "Default")
      (node (ref "C1") (pin "1") (pinfunction "1_1") (pintype "passive"))
      (node (ref "JP1") (pin "3") (pinfunction "3_3") (pintype "passive"))
      (node (ref "P2") (pin "3") (pinfunction "3_3") (pintype "passive"))
    )
    (net (code "29") (name "/RSSI") (class "Default")
      (node (ref "P2") (pin "7") (pinfunction "7_7") (pintype "passive"))
      (node (ref "U1") (pin "16") (pinfunction "RSSI_16") (pintype "passive"))
    )
    (net (code "30") (name "/RXTX") (class "Default")
      (node (ref "P1") (pin "9") (pinfunction "9_9") (pintype "passive"))
      (node (ref "U1") (pin "48") (pinfunction "RXTX_48") (pintype "passive"))
    )
    (net (code "31") (name "/SCL") (class "Default")
      (node (ref "P1") (pin "1") (pinfunction "1_1") (pintype "passive"))
      (node (ref "R21") (pin "2") (pinfunction "2_2") (pintype "passive"))
      (node (ref "U5") (pin "4") (pinfunction "SCL_4") (pintype "passive"))
    )
    (net (code "32") (name "/SCLK") (class "Default")
      (node (ref "P1") (pin "8") (pinfunction "8_8") (pintype "passive"))
      (node (ref "U1") (pin "18") (pinfunction "SCLK_18") (pintype "passive"))
    )
    (net (code "33") (name "/SDA") (class "Default")
      (node (ref "P1") (pin "7") (pinfunction "7_7") (pintype "passive"))
      (node (ref "R20") (pin "2") (pinfunction "2_2") (pintype "passive"))
      (node (ref "U5") (pin "5") (pinfunction "SDA_5") (pintype "passive"))
    )
    (net (code "34") (name "/SHDN") (class "Default")
      (node (ref "P1") (pin "4") (pinfunction "4_4") (pintype "passive"))
      (node (ref "U1") (pin "12") (pinfunction "SHDN_12") (pintype "passive"))
    )
    (net (code "35") (name "AGND") (class "Default")
      (node (ref "C10") (pin "1") (pinfunction "1_1") (pintype "passive"))
      (node (ref "C11") (pin "2") (pinfunction "2_2") (pintype "passive"))
      (node (ref "C12") (pin "2") (pinfunction "2_2") (pintype "passive"))
      (node (ref "C13") (pin "2") (pinfunction "2_2") (pintype "passive"))
      (node (ref "C14") (pin "2") (pinfunction "2_2") (pintype "passive"))
      (node (ref "C15") (pin "2") (pinfunction "2_2") (pintype "passive"))
      (node (ref "C16") (pin "2") (pinfunction "2_2") (pintype "passive"))
      (node (ref "C17") (pin "2") (pinfunction "2_2") (pintype "passive"))
      (node (ref "C18") (pin "1") (pinfunction "1_1") (pintype "passive"))
      (node (ref "C19") (pin "2") (pinfunction "2_2") (pintype "passive"))
      (node (ref "C2") (pin "1") (pinfunction "1_1") (pintype "passive"))
      (node (ref "C20") (pin "2") (pinfunction "2_2") (pintype "passive"))
      (node (ref "C21") (pin "2") (pinfunction "2_2") (pintype "passive"))
      (node (ref "C22") (pin "2") (pinfunction "2_2") (pintype "passive"))
      (node (ref "C23") (pin "2") (pinfunction "2_2") (pintype "passive"))
      (node (ref "C24") (pin "2") (pinfunction "2_2") (pintype "passive"))
      (node (ref "C25") (pin "2") (pinfunction "2_2") (pintype "passive"))
      (node (ref "C26") (pin "2") (pinfunction "2_2") (pintype "passive"))
      (node (ref "C27") (pin "2") (pinfunction "2_2") (pintype "passive"))
      (node (ref "C28") (pin "2") (pinfunction "2_2") (pintype "passive"))
      (node (ref "C29") (pin "2") (pinfunction "2_2") (pintype "passive"))
      (node (ref "C3") (pin "1") (pinfunction "1_1") (pintype "passive"))
      (node (ref "C30") (pin "2") (pinfunction "2_2") (pintype "passive"))
      (node (ref "C31") (pin "2") (pinfunction "2_2") (pintype "passive"))
      (node (ref "C32") (pin "2") (pinfunction "2_2") (pintype "passive"))
      (node (ref "C33") (pin "2") (pinfunction "2_2") (pintype "passive"))
      (node (ref "C34") (pin "2") (pinfunction "2_2") (pintype "passive"))
      (node (ref "C35") (pin "2") (pinfunction "2_2") (pintype "passive"))
      (node (ref "C36") (pin "2") (pinfunction "2_2") (pintype "passive"))
      (node (ref "C37") (pin "2") (pinfunction "2_2") (pintype "passive"))
      (node (ref "C38") (pin "2") (pinfunction "2_2") (pintype "passive"))
      (node (ref "C39") (pin "2") (pinfunction "2_2") (pintype "passive"))
      (node (ref "C4") (pin "1") (pinfunction "1_1") (pintype "passive"))
      (node (ref "C40") (pin "2") (pinfunction "2_2") (pintype "passive"))
      (node (ref "C41") (pin "2") (pinfunction "2_2") (pintype "passive"))
      (node (ref "C5") (pin "1") (pinfunction "1_1") (pintype "passive"))
      (node (ref "C6") (pin "1") (pinfunction "1_1") (pintype "passive"))
      (node (ref "C7") (pin "1") (pinfunction "1_1") (pintype "passive"))
      (node (ref "C8") (pin "1") (pinfunction "1_1") (pintype "passive"))
      (node (ref "C9") (pin "1") (pinfunction "1_1") (pintype "passive"))
      (node (ref "L1") (pin "2") (pinfunction "GND_2") (pintype "passive"))
      (node (ref "L1") (pin "5") (pinfunction "GND_5") (pintype "passive"))
      (node (ref "P1") (pin "11") (pinfunction "11_11") (pintype "passive"))
      (node (ref "P1") (pin "5") (pinfunction "5_5") (pintype "passive"))
      (node (ref "P2") (pin "11") (pinfunction "11_11") (pintype "passive"))
      (node (ref "P2") (pin "5") (pinfunction "5_5") (pintype "passive"))
      (node (ref "P3") (pin "11") (pinfunction "11_11") (pintype "passive"))
      (node (ref "P3") (pin "5") (pinfunction "5_5") (pintype "passive"))
      (node (ref "P4") (pin "11") (pinfunction "11_11") (pintype "passive"))
      (node (ref "P4") (pin "5") (pinfunction "5_5") (pintype "passive"))
      (node (ref "P5") (pin "11") (pinfunction "11_11") (pintype "passive"))
      (node (ref "P5") (pin "5") (pinfunction "5_5") (pintype "passive"))
      (node (ref "P6") (pin "11") (pinfunction "11_11") (pintype "passive"))
      (node (ref "P6") (pin "5") (pinfunction "5_5") (pintype "passive"))
      (node (ref "P7") (pin "2") (pinfunction "2_2") (pintype "passive"))
      (node (ref "P8") (pin "GND") (pinfunction "Y_GND") (pintype "passive"))
      (node (ref "R14") (pin "2") (pinfunction "2_2") (pintype "passive"))
      (node (ref "R15") (pin "2") (pinfunction "2_2") (pintype "passive"))
      (node (ref "R16") (pin "2") (pinfunction "2_2") (pintype "passive"))
      (node (ref "R17") (pin "2") (pinfunction "2_2") (pintype "passive"))
      (node (ref "R18") (pin "2") (pinfunction "2_2") (pintype "passive"))
      (node (ref "R3") (pin "2") (pinfunction "2_2") (pintype "passive"))
      (node (ref "R6") (pin "2") (pinfunction "2_2") (pintype "passive"))
      (node (ref "R7") (pin "2") (pinfunction "2_2") (pintype "passive"))
      (node (ref "R8") (pin "2") (pinfunction "2_2") (pintype "passive"))
      (node (ref "R9") (pin "2") (pinfunction "2_2") (pintype "passive"))
      (node (ref "U1") (pin "2") (pinfunction "GND_RX_LNA_2") (pintype "passive"))
      (node (ref "U1") (pin "26") (pinfunction "GND_CP_26") (pintype "passive"))
      (node (ref "U1") (pin "31") (pinfunction "GND_VCO_31") (pintype "passive"))
      (node (ref "U1") (pin "40") (pinfunction "RX_HP_40") (pintype "passive"))
      (node (ref "U2") (pin "12") (pinfunction "DB6_12") (pintype "passive"))
      (node (ref "U2") (pin "13") (pinfunction "DB5_13") (pintype "passive"))
      (node (ref "U2") (pin "14") (pinfunction "DB4_14") (pintype "passive"))
      (node (ref "U2") (pin "15") (pinfunction "DB3_15") (pintype "passive"))
      (node (ref "U2") (pin "17") (pinfunction "D_GND_17") (pintype "passive"))
      (node (ref "U2") (pin "18") (pinfunction "DB2_18") (pintype "passive"))
      (node (ref "U2") (pin "19") (pinfunction "DB1_19") (pintype "passive"))
      (node (ref "U2") (pin "20") (pinfunction "DB0_20") (pintype "passive"))
      (node (ref "U2") (pin "25") (pinfunction "CLK_X_P_25") (pintype "passive"))
      (node (ref "U2") (pin "29") (pinfunction "C_GND_29") (pintype "passive"))
      (node (ref "U2") (pin "36") (pinfunction "A_GND_36") (pintype "passive"))
      (node (ref "U2") (pin "40") (pinfunction "A_GND_40") (pintype "passive"))
      (node (ref "U2") (pin "41") (pinfunction "GND_41") (pintype "passive"))
      (node (ref "U3") (pin "10") (pinfunction "GND_10") (pintype "passive"))
      (node (ref "U3") (pin "13") (pinfunction "GND_13") (pintype "passive"))
      (node (ref "U3") (pin "16") (pinfunction "GND_16") (pintype "passive"))
      (node (ref "U3") (pin "3") (pinfunction "GND_3") (pintype "passive"))
      (node (ref "U3") (pin "31") (pinfunction "O_GND_31") (pintype "passive"))
      (node (ref "U3") (pin "34") (pinfunction "O_GND_34") (pintype "passive"))
      (node (ref "U3") (pin "7") (pinfunction "GND_7") (pintype "passive"))
      (node (ref "U4") (pin "2") (pinfunction "GND_2") (pintype "passive"))
      (node (ref "U5") (pin "21") (pinfunction "GND_21") (pintype "passive"))
      (node (ref "U5") (pin "7") (pinfunction "OEB_7") (pintype "passive"))
      (node (ref "X1") (pin "10") (pinfunction "AFC_10") (pintype "passive"))
      (node (ref "X1") (pin "4") (pinfunction "GND_4") (pintype "passive"))
      (node (ref "X2") (pin "GND") (pinfunction "GND_GND") (pintype "passive"))
    )
    (net (code "36") (name "Net-(C3-Pad2)") (class "Default")
      (node (ref "C3") (pin "2") (pinfunction "2_2") (pintype "passive"))
      (node (ref "R2") (pin "1") (pinfunction "1_1") (pintype "passive"))
    )
    (net (code "37") (name "Net-(L1-UB)") (class "Default")
      (node (ref "L1") (pin "1") (pinfunction "UB_1") (pintype "passive"))
      (node (ref "P8") (pin "SIGNAL") (pinfunction "X_SIGNAL") (pintype "passive"))
    )
    (net (code "38") (name "Net-(P4-Pad1)") (class "Default")
      (node (ref "P4") (pin "1") (pinfunction "1_1") (pintype "passive"))
      (node (ref "R39") (pin "1") (pinfunction "1_1") (pintype "passive"))
    )
    (net (code "39") (name "Net-(P4-Pad2)") (class "Default")
      (node (ref "P4") (pin "2") (pinfunction "2_2") (pintype "passive"))
      (node (ref "R37") (pin "1") (pinfunction "1_1") (pintype "passive"))
    )
    (net (code "40") (name "Net-(P4-Pad3)") (class "Default")
      (node (ref "P4") (pin "3") (pinfunction "3_3") (pintype "passive"))
      (node (ref "R35") (pin "1") (pinfunction "1_1") (pintype "passive"))
    )
    (net (code "41") (name "Net-(P4-Pad4)") (class "Default")
      (node (ref "P4") (pin "4") (pinfunction "4_4") (pintype "passive"))
      (node (ref "R33") (pin "1") (pinfunction "1_1") (pintype "passive"))
    )
    (net (code "42") (name "Net-(P4-Pad7)") (class "Default")
      (node (ref "P4") (pin "7") (pinfunction "7_7") (pintype "passive"))
      (node (ref "R38") (pin "1") (pinfunction "1_1") (pintype "passive"))
    )
    (net (code "43") (name "Net-(P4-Pad8)") (class "Default")
      (node (ref "P4") (pin "8") (pinfunction "8_8") (pintype "passive"))
      (node (ref "R36") (pin "1") (pinfunction "1_1") (pintype "passive"))
    )
    (net (code "44") (name "Net-(P4-Pad9)") (class "Default")
      (node (ref "P4") (pin "9") (pinfunction "9_9") (pintype "passive"))
      (node (ref "R34") (pin "1") (pinfunction "1_1") (pintype "passive"))
    )
    (net (code "45") (name "Net-(P4-Pad10)") (class "Default")
      (node (ref "P4") (pin "10") (pinfunction "10_10") (pintype "passive"))
      (node (ref "R32") (pin "1") (pinfunction "1_1") (pintype "passive"))
    )
    (net (code "46") (name "Net-(P5-Pad1)") (class "Default")
      (node (ref "P5") (pin "1") (pinfunction "1_1") (pintype "passive"))
      (node (ref "R24") (pin "1") (pinfunction "1_1") (pintype "passive"))
    )
    (net (code "47") (name "Net-(P5-Pad2)") (class "Default")
      (node (ref "P5") (pin "2") (pinfunction "2_2") (pintype "passive"))
      (node (ref "R26") (pin "1") (pinfunction "1_1") (pintype "passive"))
    )
    (net (code "48") (name "Net-(P5-Pad3)") (class "Default")
      (node (ref "P5") (pin "3") (pinfunction "3_3") (pintype "passive"))
      (node (ref "R28") (pin "1") (pinfunction "1_1") (pintype "passive"))
    )
    (net (code "49") (name "Net-(P5-Pad4)") (class "Default")
      (node (ref "P5") (pin "4") (pinfunction "4_4") (pintype "passive"))
      (node (ref "R30") (pin "1") (pinfunction "1_1") (pintype "passive"))
    )
    (net (code "50") (name "Net-(P5-Pad7)") (class "Default")
      (node (ref "P5") (pin "7") (pinfunction "7_7") (pintype "passive"))
      (node (ref "R25") (pin "1") (pinfunction "1_1") (pintype "passive"))
    )
    (net (code "51") (name "Net-(P5-Pad8)") (class "Default")
      (node (ref "P5") (pin "8") (pinfunction "8_8") (pintype "passive"))
      (node (ref "R27") (pin "1") (pinfunction "1_1") (pintype "passive"))
    )
    (net (code "52") (name "Net-(P5-Pad9)") (class "Default")
      (node (ref "P5") (pin "9") (pinfunction "9_9") (pintype "passive"))
      (node (ref "R29") (pin "1") (pinfunction "1_1") (pintype "passive"))
    )
    (net (code "53") (name "Net-(P5-Pad10)") (class "Default")
      (node (ref "P5") (pin "10") (pinfunction "10_10") (pintype "passive"))
      (node (ref "R31") (pin "1") (pinfunction "1_1") (pintype "passive"))
    )
    (net (code "54") (name "Net-(P6-Pad1)") (class "Default")
      (node (ref "P6") (pin "1") (pinfunction "1_1") (pintype "passive"))
      (node (ref "R40") (pin "1") (pinfunction "1_1") (pintype "passive"))
    )
    (net (code "55") (name "Net-(P6-Pad2)") (class "Default")
      (node (ref "P6") (pin "2") (pinfunction "2_2") (pintype "passive"))
      (node (ref "R42") (pin "1") (pinfunction "1_1") (pintype "passive"))
    )
    (net (code "56") (name "Net-(P6-Pad3)") (class "Default")
      (node (ref "P6") (pin "3") (pinfunction "3_3") (pintype "passive"))
      (node (ref "R44") (pin "1") (pinfunction "1_1") (pintype "passive"))
    )
    (net (code "57") (name "Net-(P6-Pad4)") (class "Default")
      (node (ref "P6") (pin "4") (pinfunction "4_4") (pintype "passive"))
      (node (ref "R46") (pin "1") (pinfunction "1_1") (pintype "passive"))
    )
    (net (code "58") (name "Net-(P6-Pad7)") (class "Default")
      (node (ref "P6") (pin "7") (pinfunction "7_7") (pintype "passive"))
      (node (ref "R41") (pin "1") (pinfunction "1_1") (pintype "passive"))
    )
    (net (code "59") (name "Net-(P6-Pad8)") (class "Default")
      (node (ref "P6") (pin "8") (pinfunction "8_8") (pintype "passive"))
      (node (ref "R43") (pin "1") (pinfunction "1_1") (pintype "passive"))
    )
    (net (code "60") (name "Net-(P6-Pad9)") (class "Default")
      (node (ref "P6") (pin "9") (pinfunction "9_9") (pintype "passive"))
      (node (ref "R45") (pin "1") (pinfunction "1_1") (pintype "passive"))
    )
    (net (code "61") (name "Net-(P6-Pad10)") (class "Default")
      (node (ref "P6") (pin "10") (pinfunction "10_10") (pintype "passive"))
      (node (ref "R47") (pin "1") (pinfunction "1_1") (pintype "passive"))
    )
    (net (code "62") (name "Net-(U1-ANTSEL)") (class "Default")
      (node (ref "R4") (pin "1") (pinfunction "1_1") (pintype "passive"))
      (node (ref "U1") (pin "47") (pinfunction "ANTSEL_47") (pintype "passive"))
    )
    (net (code "63") (name "Net-(U1-BYPASS)") (class "Default")
      (node (ref "C5") (pin "2") (pinfunction "2_2") (pintype "passive"))
      (node (ref "U1") (pin "33") (pinfunction "BYPASS_33") (pintype "passive"))
    )
    (net (code "64") (name "Net-(U1-CP_OUT)") (class "Default")
      (node (ref "C4") (pin "2") (pinfunction "2_2") (pintype "passive"))
      (node (ref "R1") (pin "2") (pinfunction "2_2") (pintype "passive"))
      (node (ref "R2") (pin "2") (pinfunction "2_2") (pintype "passive"))
      (node (ref "U1") (pin "24") (pinfunction "CP_OUT_24") (pintype "passive"))
    )
    (net (code "65") (name "Net-(U1-TUNE)") (class "Default")
      (node (ref "C2") (pin "2") (pinfunction "2_2") (pintype "passive"))
      (node (ref "R1") (pin "1") (pinfunction "1_1") (pintype "passive"))
      (node (ref "U1") (pin "32") (pinfunction "TUNE_32") (pintype "passive"))
    )
    (net (code "66") (name "Net-(U1-XTAL)") (class "Default")
      (node (ref "C1") (pin "2") (pinfunction "2_2") (pintype "passive"))
      (node (ref "R3") (pin "1") (pinfunction "1_1") (pintype "passive"))
      (node (ref "U1") (pin "28") (pinfunction "XTAL_28") (pintype "passive"))
    )
    (net (code "67") (name "Net-(U2-CLK_X_N)") (class "Default")
      (node (ref "R11") (pin "1") (pinfunction "1_1") (pintype "passive"))
      (node (ref "U2") (pin "26") (pinfunction "CLK_X_N_26") (pintype "passive"))
    )
    (net (code "68") (name "Net-(U2-DA0)") (class "Default")
      (node (ref "R40") (pin "2") (pinfunction "2_2") (pintype "passive"))
      (node (ref "U2") (pin "8") (pinfunction "DA0_8") (pintype "passive"))
    )
    (net (code "69") (name "Net-(U2-DA1)") (class "Default")
      (node (ref "R41") (pin "2") (pinfunction "2_2") (pintype "passive"))
      (node (ref "U2") (pin "7") (pinfunction "DA1_7") (pintype "passive"))
    )
    (net (code "70") (name "Net-(U2-DA2)") (class "Default")
      (node (ref "R42") (pin "2") (pinfunction "2_2") (pintype "passive"))
      (node (ref "U2") (pin "6") (pinfunction "DA2_6") (pintype "passive"))
    )
    (net (code "71") (name "Net-(U2-DA3)") (class "Default")
      (node (ref "R43") (pin "2") (pinfunction "2_2") (pintype "passive"))
      (node (ref "U2") (pin "5") (pinfunction "DA3_5") (pintype "passive"))
    )
    (net (code "72") (name "Net-(U2-DA4)") (class "Default")
      (node (ref "R44") (pin "2") (pinfunction "2_2") (pintype "passive"))
      (node (ref "U2") (pin "4") (pinfunction "DA4_4") (pintype "passive"))
    )
    (net (code "73") (name "Net-(U2-DA5)") (class "Default")
      (node (ref "R45") (pin "2") (pinfunction "2_2") (pintype "passive"))
      (node (ref "U2") (pin "3") (pinfunction "DA5_3") (pintype "passive"))
    )
    (net (code "74") (name "Net-(U2-DA6)") (class "Default")
      (node (ref "R46") (pin "2") (pinfunction "2_2") (pintype "passive"))
      (node (ref "U2") (pin "2") (pinfunction "DA6_2") (pintype "passive"))
    )
    (net (code "75") (name "Net-(U2-DA7)") (class "Default")
      (node (ref "R47") (pin "2") (pinfunction "2_2") (pintype "passive"))
      (node (ref "U2") (pin "1") (pinfunction "DA7_1") (pintype "passive"))
    )
    (net (code "76") (name "Net-(U2-DCE)") (class "Default")
      (node (ref "R12") (pin "1") (pinfunction "1_1") (pintype "passive"))
      (node (ref "U2") (pin "24") (pinfunction "DCE_24") (pintype "passive"))
    )
    (net (code "77") (name "Net-(U2-REF_O)") (class "Default")
      (node (ref "C6") (pin "2") (pinfunction "2_2") (pintype "passive"))
      (node (ref "U2") (pin "31") (pinfunction "REF_O_31") (pintype "passive"))
    )
    (net (code "78") (name "Net-(U2-REF_R)") (class "Default")
      (node (ref "R14") (pin "1") (pinfunction "1_1") (pintype "passive"))
      (node (ref "U2") (pin "32") (pinfunction "REF_R_32") (pintype "passive"))
    )
    (net (code "79") (name "Net-(U3-COM)") (class "Default")
      (node (ref "C7") (pin "2") (pinfunction "2_2") (pintype "passive"))
      (node (ref "U3") (pin "1") (pinfunction "COM_1") (pintype "passive"))
    )
    (net (code "80") (name "Net-(U3-D0_A)") (class "Default")
      (node (ref "R32") (pin "2") (pinfunction "2_2") (pintype "passive"))
      (node (ref "U3") (pin "37") (pinfunction "D0_A_37") (pintype "passive"))
    )
    (net (code "81") (name "Net-(U3-D0_B)") (class "Default")
      (node (ref "R24") (pin "2") (pinfunction "2_2") (pintype "passive"))
      (node (ref "U3") (pin "28") (pinfunction "D0_B_28") (pintype "passive"))
    )
    (net (code "82") (name "Net-(U3-D1_A)") (class "Default")
      (node (ref "R33") (pin "2") (pinfunction "2_2") (pintype "passive"))
      (node (ref "U3") (pin "38") (pinfunction "D1_A_38") (pintype "passive"))
    )
    (net (code "83") (name "Net-(U3-D1_B)") (class "Default")
      (node (ref "R25") (pin "2") (pinfunction "2_2") (pintype "passive"))
      (node (ref "U3") (pin "27") (pinfunction "D1_B_27") (pintype "passive"))
    )
    (net (code "84") (name "Net-(U3-D2_A)") (class "Default")
      (node (ref "R34") (pin "2") (pinfunction "2_2") (pintype "passive"))
      (node (ref "U3") (pin "39") (pinfunction "D2_A_39") (pintype "passive"))
    )
    (net (code "85") (name "Net-(U3-D2_B)") (class "Default")
      (node (ref "R26") (pin "2") (pinfunction "2_2") (pintype "passive"))
      (node (ref "U3") (pin "26") (pinfunction "D2_B_26") (pintype "passive"))
    )
    (net (code "86") (name "Net-(U3-D3_A)") (class "Default")
      (node (ref "R35") (pin "2") (pinfunction "2_2") (pintype "passive"))
      (node (ref "U3") (pin "40") (pinfunction "D3_A_40") (pintype "passive"))
    )
    (net (code "87") (name "Net-(U3-D3_B)") (class "Default")
      (node (ref "R27") (pin "2") (pinfunction "2_2") (pintype "passive"))
      (node (ref "U3") (pin "25") (pinfunction "D3_B_25") (pintype "passive"))
    )
    (net (code "88") (name "Net-(U3-D4_A)") (class "Default")
      (node (ref "R36") (pin "2") (pinfunction "2_2") (pintype "passive"))
      (node (ref "U3") (pin "41") (pinfunction "D4_A_41") (pintype "passive"))
    )
    (net (code "89") (name "Net-(U3-D4_B)") (class "Default")
      (node (ref "R28") (pin "2") (pinfunction "2_2") (pintype "passive"))
      (node (ref "U3") (pin "24") (pinfunction "D4_B_24") (pintype "passive"))
    )
    (net (code "90") (name "Net-(U3-D5_A)") (class "Default")
      (node (ref "R37") (pin "2") (pinfunction "2_2") (pintype "passive"))
      (node (ref "U3") (pin "42") (pinfunction "D5_A_42") (pintype "passive"))
    )
    (net (code "91") (name "Net-(U3-D5_B)") (class "Default")
      (node (ref "R29") (pin "2") (pinfunction "2_2") (pintype "passive"))
      (node (ref "U3") (pin "23") (pinfunction "D5_B_23") (pintype "passive"))
    )
    (net (code "92") (name "Net-(U3-D6_A)") (class "Default")
      (node (ref "R38") (pin "2") (pinfunction "2_2") (pintype "passive"))
      (node (ref "U3") (pin "43") (pinfunction "D6_A_43") (pintype "passive"))
    )
    (net (code "93") (name "Net-(U3-D6_B)") (class "Default")
      (node (ref "R30") (pin "2") (pinfunction "2_2") (pintype "passive"))
      (node (ref "U3") (pin "22") (pinfunction "D6_B_22") (pintype "passive"))
    )
    (net (code "94") (name "Net-(U3-D7_A)") (class "Default")
      (node (ref "R39") (pin "2") (pinfunction "2_2") (pintype "passive"))
      (node (ref "U3") (pin "44") (pinfunction "D7_A_44") (pintype "passive"))
    )
    (net (code "95") (name "Net-(U3-D7_B)") (class "Default")
      (node (ref "R31") (pin "2") (pinfunction "2_2") (pintype "passive"))
      (node (ref "U3") (pin "21") (pinfunction "D7_B_21") (pintype "passive"))
    )
    (net (code "96") (name "Net-(U3-OE)") (class "Default")
      (node (ref "R7") (pin "1") (pinfunction "1_1") (pintype "passive"))
      (node (ref "U3") (pin "20") (pinfunction "OE_20") (pintype "passive"))
    )
    (net (code "97") (name "Net-(U3-PD)") (class "Default")
      (node (ref "R8") (pin "1") (pinfunction "1_1") (pintype "passive"))
      (node (ref "U3") (pin "19") (pinfunction "PD_19") (pintype "passive"))
    )
    (net (code "98") (name "Net-(U3-REF_IN)") (class "Default")
      (node (ref "C8") (pin "2") (pinfunction "2_2") (pintype "passive"))
      (node (ref "R5") (pin "2") (pinfunction "2_2") (pintype "passive"))
      (node (ref "R6") (pin "1") (pinfunction "1_1") (pintype "passive"))
      (node (ref "U3") (pin "46") (pinfunction "REF_IN_46") (pintype "passive"))
    )
    (net (code "99") (name "Net-(U3-REF_N)") (class "Default")
      (node (ref "C10") (pin "2") (pinfunction "2_2") (pintype "passive"))
      (node (ref "U3") (pin "48") (pinfunction "REF_N_48") (pintype "passive"))
    )
    (net (code "100") (name "Net-(U3-REF_OUT)") (class "Default")
      (node (ref "R5") (pin "1") (pinfunction "1_1") (pintype "passive"))
      (node (ref "U3") (pin "45") (pinfunction "REF_OUT_45") (pintype "passive"))
    )
    (net (code "101") (name "Net-(U3-REF_P)") (class "Default")
      (node (ref "C9") (pin "2") (pinfunction "2_2") (pintype "passive"))
      (node (ref "U3") (pin "47") (pinfunction "REF_P_47") (pintype "passive"))
    )
    (net (code "102") (name "Net-(U3-SLEEP)") (class "Default")
      (node (ref "R9") (pin "1") (pinfunction "1_1") (pintype "passive"))
      (node (ref "U3") (pin "18") (pinfunction "SLEEP_18") (pintype "passive"))
    )
    (net (code "103") (name "Net-(U3-T{slash}B)") (class "Default")
      (node (ref "R10") (pin "1") (pinfunction "1_1") (pintype "passive"))
      (node (ref "U3") (pin "17") (pinfunction "T/B_17") (pintype "passive"))
    )
    (net (code "104") (name "Net-(U4-EN)") (class "Default")
      (node (ref "R23") (pin "1") (pinfunction "1_1") (pintype "passive"))
      (node (ref "U4") (pin "1") (pinfunction "EN_1") (pintype "passive"))
    )
    (net (code "105") (name "Net-(U5-CLK_IN)") (class "Default")
      (node (ref "U5") (pin "6") (pinfunction "CLK_IN_6") (pintype "passive"))
      (node (ref "X1") (pin "5") (pinfunction "OUT_5") (pintype "passive"))
    )
    (net (code "106") (name "Net-(X1-3S)") (class "Default")
      (node (ref "R19") (pin "1") (pinfunction "1_1") (pintype "passive"))
      (node (ref "X1") (pin "8") (pinfunction "3S_8") (pintype "passive"))
    )
    (net (code "107") (name "VCC") (class "Default")
      (node (ref "C11") (pin "1") (pinfunction "1_1") (pintype "passive"))
      (node (ref "C13") (pin "1") (pinfunction "1_1") (pintype "passive"))
      (node (ref "C14") (pin "1") (pinfunction "1_1") (pintype "passive"))
      (node (ref "C15") (pin "1") (pinfunction "1_1") (pintype "passive"))
      (node (ref "C16") (pin "1") (pinfunction "1_1") (pintype "passive"))
      (node (ref "C17") (pin "1") (pinfunction "1_1") (pintype "passive"))
      (node (ref "C18") (pin "2") (pinfunction "2_2") (pintype "passive"))
      (node (ref "C19") (pin "1") (pinfunction "1_1") (pintype "passive"))
      (node (ref "C20") (pin "1") (pinfunction "1_1") (pintype "passive"))
      (node (ref "C21") (pin "1") (pinfunction "1_1") (pintype "passive"))
      (node (ref "C22") (pin "1") (pinfunction "1_1") (pintype "passive"))
      (node (ref "C23") (pin "1") (pinfunction "1_1") (pintype "passive"))
      (node (ref "C24") (pin "1") (pinfunction "1_1") (pintype "passive"))
      (node (ref "C25") (pin "1") (pinfunction "1_1") (pintype "passive"))
      (node (ref "C26") (pin "1") (pinfunction "1_1") (pintype "passive"))
      (node (ref "C27") (pin "1") (pinfunction "1_1") (pintype "passive"))
      (node (ref "C28") (pin "1") (pinfunction "1_1") (pintype "passive"))
      (node (ref "C29") (pin "1") (pinfunction "1_1") (pintype "passive"))
      (node (ref "C30") (pin "1") (pinfunction "1_1") (pintype "passive"))
      (node (ref "C31") (pin "1") (pinfunction "1_1") (pintype "passive"))
      (node (ref "C32") (pin "1") (pinfunction "1_1") (pintype "passive"))
      (node (ref "C33") (pin "1") (pinfunction "1_1") (pintype "passive"))
      (node (ref "C34") (pin "1") (pinfunction "1_1") (pintype "passive"))
      (node (ref "C35") (pin "1") (pinfunction "1_1") (pintype "passive"))
      (node (ref "C36") (pin "1") (pinfunction "1_1") (pintype "passive"))
      (node (ref "C37") (pin "1") (pinfunction "1_1") (pintype "passive"))
      (node (ref "C38") (pin "1") (pinfunction "1_1") (pintype "passive"))
      (node (ref "C39") (pin "1") (pinfunction "1_1") (pintype "passive"))
      (node (ref "C40") (pin "1") (pinfunction "1_1") (pintype "passive"))
      (node (ref "C41") (pin "1") (pinfunction "1_1") (pintype "passive"))
      (node (ref "P7") (pin "3") (pinfunction "3_3") (pintype "passive"))
      (node (ref "R10") (pin "2") (pinfunction "2_2") (pintype "passive"))
      (node (ref "R11") (pin "2") (pinfunction "2_2") (pintype "passive"))
      (node (ref "R12") (pin "2") (pinfunction "2_2") (pintype "passive"))
      (node (ref "R13") (pin "2") (pinfunction "2_2") (pintype "passive"))
      (node (ref "R19") (pin "2") (pinfunction "2_2") (pintype "passive"))
      (node (ref "R20") (pin "1") (pinfunction "1_1") (pintype "passive"))
      (node (ref "R21") (pin "1") (pinfunction "1_1") (pintype "passive"))
      (node (ref "R22") (pin "1") (pinfunction "1_1") (pintype "passive"))
      (node (ref "R4") (pin "2") (pinfunction "2_2") (pintype "passive"))
      (node (ref "U1") (pin "1") (pinfunction "V_CC_LNA_1") (pintype "passive"))
      (node (ref "U1") (pin "13") (pinfunction "V_CC_TX_PA_13") (pintype "passive"))
      (node (ref "U1") (pin "17") (pinfunction "V_CC_TX_MX_17") (pintype "passive"))
      (node (ref "U1") (pin "20") (pinfunction "V_CC_PLL_20") (pintype "passive"))
      (node (ref "U1") (pin "25") (pinfunction "V_CC_CP_25") (pintype "passive"))
      (node (ref "U1") (pin "27") (pinfunction "V_CC_XTAL_27") (pintype "passive"))
      (node (ref "U1") (pin "30") (pinfunction "V_CC_VCO_30") (pintype "passive"))
      (node (ref "U1") (pin "39") (pinfunction "V_CC_RX_VGA_39") (pintype "passive"))
      (node (ref "U1") (pin "41") (pinfunction "V_CC_RX_FL_41") (pintype "passive"))
      (node (ref "U1") (pin "46") (pinfunction "V_CC_RX_MX_46") (pintype "passive"))
      (node (ref "U1") (pin "7") (pinfunction "V_CC_PA_7") (pintype "passive"))
      (node (ref "U2") (pin "11") (pinfunction "DB7_11") (pintype "passive"))
      (node (ref "U2") (pin "16") (pinfunction "D_V_DD_16") (pintype "passive"))
      (node (ref "U2") (pin "27") (pinfunction "C_V_DD_27") (pintype "passive"))
      (node (ref "U2") (pin "30") (pinfunction "C_V_DD_30") (pintype "passive"))
      (node (ref "U2") (pin "33") (pinfunction "A_V_DD_33") (pintype "passive"))
      (node (ref "U2") (pin "39") (pinfunction "A_V_DD_39") (pintype "passive"))
      (node (ref "U3") (pin "11") (pinfunction "V_DD_11") (pintype "passive"))
      (node (ref "U3") (pin "14") (pinfunction "V_DD_14") (pintype "passive"))
      (node (ref "U3") (pin "15") (pinfunction "V_DD_15") (pintype "passive"))
      (node (ref "U3") (pin "2") (pinfunction "V_DD_2") (pintype "passive"))
      (node (ref "U3") (pin "32") (pinfunction "O_V_DD_32") (pintype "passive"))
      (node (ref "U3") (pin "33") (pinfunction "O_V_DD_33") (pintype "passive"))
      (node (ref "U3") (pin "6") (pinfunction "V_DD_6") (pintype "passive"))
      (node (ref "U4") (pin "5") (pinfunction "V_OUT_5") (pintype "passive"))
      (node (ref "U5") (pin "10") (pinfunction "V_DD_OB_10") (pintype "passive"))
      (node (ref "U5") (pin "11") (pinfunction "V_DD_OA_11") (pintype "passive"))
      (node (ref "U5") (pin "14") (pinfunction "V_DD_OD_14") (pintype "passive"))
      (node (ref "U5") (pin "18") (pinfunction "V_DD_OC_18") (pintype "passive"))
      (node (ref "U5") (pin "20") (pinfunction "V_DD_20") (pintype "passive"))
      (node (ref "X1") (pin "9") (pinfunction "V_CC_9") (pintype "passive"))
    )
    (net (code "108") (name "V_IN") (class "Default")
      (node (ref "C12") (pin "1") (pinfunction "1_1") (pintype "passive"))
      (node (ref "P1") (pin "12") (pinfunction "12_12") (pintype "passive"))
      (node (ref "P1") (pin "6") (pinfunction "6_6") (pintype "passive"))
      (node (ref "P2") (pin "12") (pinfunction "12_12") (pintype "passive"))
      (node (ref "P2") (pin "6") (pinfunction "6_6") (pintype "passive"))
      (node (ref "P3") (pin "12") (pinfunction "12_12") (pintype "passive"))
      (node (ref "P3") (pin "6") (pinfunction "6_6") (pintype "passive"))
      (node (ref "P4") (pin "12") (pinfunction "12_12") (pintype "passive"))
      (node (ref "P4") (pin "6") (pinfunction "6_6") (pintype "passive"))
      (node (ref "P5") (pin "12") (pinfunction "12_12") (pintype "passive"))
      (node (ref "P5") (pin "6") (pinfunction "6_6") (pintype "passive"))
      (node (ref "P6") (pin "12") (pinfunction "12_12") (pintype "passive"))
      (node (ref "P6") (pin "6") (pinfunction "6_6") (pintype "passive"))
      (node (ref "P7") (pin "1") (pinfunction "1_1") (pintype "passive"))
      (node (ref "R23") (pin "2") (pinfunction "2_2") (pintype "passive"))
      (node (ref "U4") (pin "4") (pinfunction "V_IN_4") (pintype "passive"))
    )
    (net (code "109") (name "unconnected-(P2-Pad4)") (class "Default")
      (node (ref "P2") (pin "4") (pinfunction "4_4") (pintype "passive"))
    )
    (net (code "110") (name "unconnected-(P2-Pad10)") (class "Default")
      (node (ref "P2") (pin "10") (pinfunction "10_10") (pintype "passive"))
    )
    (net (code "111") (name "unconnected-(U1-ANT1+-Pad4)") (class "Default")
      (node (ref "U1") (pin "4") (pinfunction "ANT1+_4") (pintype "passive+no_connect"))
    )
    (net (code "112") (name "unconnected-(U1-ANT1--Pad5)") (class "Default")
      (node (ref "U1") (pin "5") (pinfunction "ANT1-_5") (pintype "passive+no_connect"))
    )
    (net (code "113") (name "unconnected-(U1-B1-Pad23)") (class "Default")
      (node (ref "U1") (pin "23") (pinfunction "B1_23") (pintype "passive+no_connect"))
    )
    (net (code "114") (name "unconnected-(U1-B2-Pad11)") (class "Default")
      (node (ref "U1") (pin "11") (pinfunction "B2_11") (pintype "passive+no_connect"))
    )
    (net (code "115") (name "unconnected-(U1-B3-Pad8)") (class "Default")
      (node (ref "U1") (pin "8") (pinfunction "B3_8") (pintype "passive+no_connect"))
    )
    (net (code "116") (name "unconnected-(U1-B4-Pad34)") (class "Default")
      (node (ref "U1") (pin "34") (pinfunction "B4_34") (pintype "passive+no_connect"))
    )
    (net (code "117") (name "unconnected-(U1-B5-Pad14)") (class "Default")
      (node (ref "U1") (pin "14") (pinfunction "B5_14") (pintype "passive+no_connect"))
    )
    (net (code "118") (name "unconnected-(U1-B6-Pad3)") (class "Default")
      (node (ref "U1") (pin "3") (pinfunction "B6_3") (pintype "passive+no_connect"))
    )
    (net (code "119") (name "unconnected-(U1-B7-Pad6)") (class "Default")
      (node (ref "U1") (pin "6") (pinfunction "B7_6") (pintype "passive+no_connect"))
    )
    (net (code "120") (name "unconnected-(U1-CLOCK_OUT-Pad21)") (class "Default")
      (node (ref "U1") (pin "21") (pinfunction "CLOCK_OUT_21") (pintype "passive+no_connect"))
    )
    (net (code "121") (name "unconnected-(U1-CTUNE-Pad29)") (class "Default")
      (node (ref "U1") (pin "29") (pinfunction "CTUNE_29") (pintype "passive+no_connect"))
    )
  )
)
